# Connectors.net
KiCad netlist of a schematic drawn in Altium Designer
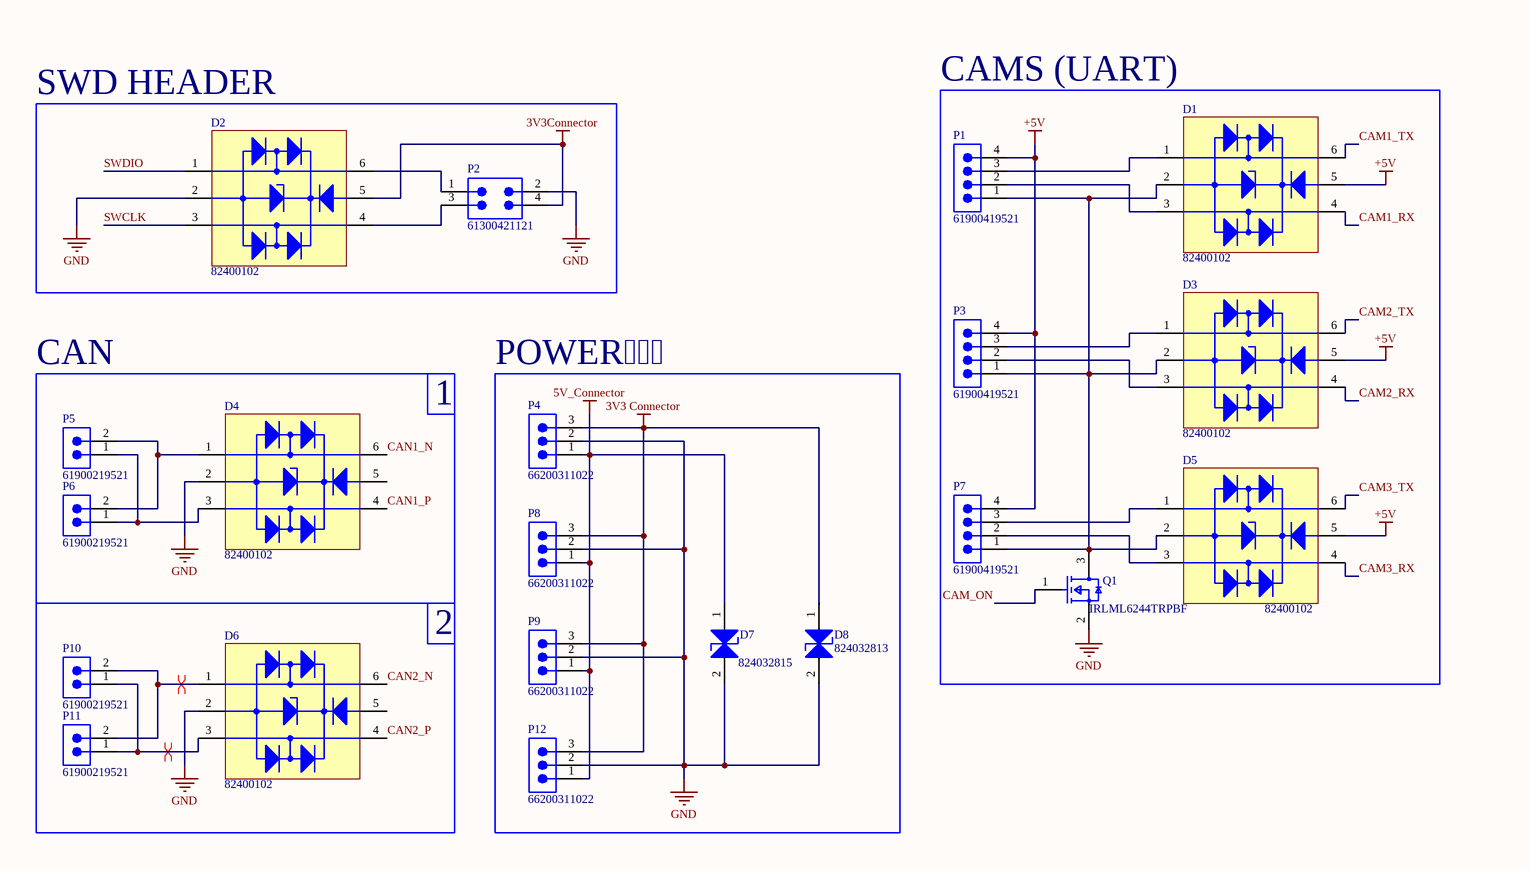
[diagram p0: Connectors.SchDoc, left]
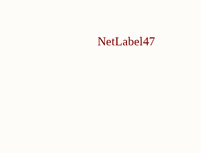
[diagram p1: Connectors.SchDoc, right]

(export (version "E")
  (design (tool "Eeschema 10.0.6"))
  (components
    (comp (ref "D1")
      (value "82400102")
      (footprint "WE-TVS_SOT23-6L")
      (description "WE-TVS TVS Diode – High Speed Series, SOT23-6L, 2+1 Channel, 5V, 2pF")
      (fields (field (name "MANUFACTURER") "Wurth Elektronik"))
      (libsource (lib "LEEM UPM") (part "82400152"))
    )
    (comp (ref "D2")
      (value "82400102")
      (footprint "WE-TVS_SOT23-6L")
      (description "WE-TVS TVS Diode – High Speed Series, SOT23-6L, 2+1 Channel, 5V, 2pF")
      (fields (field (name "MANUFACTURER") "Wurth Elektronik"))
      (libsource (lib "LEEM UPM") (part "82400152"))
    )
    (comp (ref "D3")
      (value "82400102")
      (footprint "WE-TVS_SOT23-6L")
      (description "WE-TVS TVS Diode – High Speed Series, SOT23-6L, 2+1 Channel, 5V, 2pF")
      (fields (field (name "MANUFACTURER") "Wurth Elektronik"))
      (libsource (lib "LEEM UPM") (part "82400152"))
    )
    (comp (ref "D4")
      (value "82400102")
      (footprint "WE-TVS_SOT23-6L")
      (description "WE-TVS TVS Diode – High Speed Series, SOT23-6L, 2+1 Channel, 5V, 2pF")
      (fields (field (name "MANUFACTURER") "Wurth Elektronik"))
      (libsource (lib "LEEM UPM") (part "82400152"))
    )
    (comp (ref "D5")
      (value "82400102")
      (footprint "WE-TVS_SOT23-6L")
      (description "WE-TVS TVS Diode – High Speed Series, SOT23-6L, 2+1 Channel, 5V, 2pF")
      (fields (field (name "MANUFACTURER") "Wurth Elektronik"))
      (libsource (lib "LEEM UPM") (part "82400152"))
    )
    (comp (ref "D6")
      (value "82400102")
      (footprint "WE-TVS_SOT23-6L")
      (description "WE-TVS TVS Diode – High Speed Series, SOT23-6L, 2+1 Channel, 5V, 2pF")
      (fields (field (name "MANUFACTURER") "Wurth Elektronik"))
      (libsource (lib "LEEM UPM") (part "82400152"))
    )
    (comp (ref "D7")
      (value "824032815")
      (footprint "WE-TVS_DFN1610-2L")
      (description "824032815 Tvs Diode, Bidir, 5V, Dfn1610 Rohs Compliant: Yes")
      (libsource (lib "Altium Content Vault") (part "Diode_1 Channel_Bidirectional"))
    )
    (comp (ref "D8")
      (value "824032813")
      (footprint "WE-TVS_DFN1610-2L")
      (description "824032813 Tvs Diode, Bidir, 3.3V, Dfn1610 Rohs Compliant: Yes")
      (libsource (lib "Altium Content Vault") (part "Diode_1 Channel_Bidirectional"))
    )
    (comp (ref "P1")
      (value "61900419521")
      (footprint "61900419521")
      (description "WR-WTB THT Male Right Angled Top Locking Header, pitch 2.54mm, 4pins")
      (fields (field (name "MANUFACTURER") "Wurth Elektronik"))
      (libsource (lib "LEEM UPM") (part "679304124022"))
    )
    (comp (ref "P2")
      (value "61300421121")
      (footprint "61300421121")
      (libsource (lib "LEEM UPM") (part "Header_Male_2R_04P"))
    )
    (comp (ref "P3")
      (value "61900419521")
      (footprint "61900419521")
      (description "WR-WTB THT Male Right Angled Top Locking Header, pitch 2.54mm, 4pins")
      (fields (field (name "MANUFACTURER") "Wurth Elektronik"))
      (libsource (lib "LEEM UPM") (part "679304124022"))
    )
    (comp (ref "P4")
      (value "66200311022")
      (footprint "66200311022")
      (description "WR-MPC3 THT Male Right Angled Header with Plastic Pegs, pitch 3mm, 3p")
      (fields (field (name "MANUFACTURER") "Wurth Elektronik"))
      (libsource (lib "LEEM UPM") (part "662303135922"))
    )
    (comp (ref "P5")
      (value "61900219521")
      (footprint "61900219521")
      (description "WR-WTB THT Male Right Angled Top Locking Header, pitch 2.54mm, 2pins")
      (fields (field (name "MANUFACTURER") "Wurth Elektronik"))
      (libsource (lib "LEEM UPM") (part "679302124022"))
    )
    (comp (ref "P6")
      (value "61900219521")
      (footprint "61900219521")
      (description "WR-WTB THT Male Right Angled Top Locking Header, pitch 2.54mm, 2pins")
      (fields (field (name "MANUFACTURER") "Wurth Elektronik"))
      (libsource (lib "LEEM UPM") (part "679302124022"))
    )
    (comp (ref "P7")
      (value "61900419521")
      (footprint "61900419521")
      (description "WR-WTB THT Male Right Angled Top Locking Header, pitch 2.54mm, 4pins")
      (fields (field (name "MANUFACTURER") "Wurth Elektronik"))
      (libsource (lib "LEEM UPM") (part "679304124022"))
    )
    (comp (ref "P8")
      (value "66200311022")
      (footprint "66200311022")
      (description "WR-MPC3 THT Male Right Angled Header with Plastic Pegs, pitch 3mm, 3p")
      (fields (field (name "MANUFACTURER") "Wurth Elektronik"))
      (libsource (lib "LEEM UPM") (part "662303135922"))
    )
    (comp (ref "P9")
      (value "66200311022")
      (footprint "66200311022")
      (description "WR-MPC3 THT Male Right Angled Header with Plastic Pegs, pitch 3mm, 3p")
      (fields (field (name "MANUFACTURER") "Wurth Elektronik"))
      (libsource (lib "LEEM UPM") (part "662303135922"))
    )
    (comp (ref "P10")
      (value "61900219521")
      (footprint "61900219521")
      (description "WR-WTB THT Male Right Angled Top Locking Header, pitch 2.54mm, 2pins")
      (fields (field (name "MANUFACTURER") "Wurth Elektronik"))
      (libsource (lib "LEEM UPM") (part "679302124022"))
    )
    (comp (ref "P11")
      (value "61900219521")
      (footprint "61900219521")
      (description "WR-WTB THT Male Right Angled Top Locking Header, pitch 2.54mm, 2pins")
      (fields (field (name "MANUFACTURER") "Wurth Elektronik"))
      (libsource (lib "LEEM UPM") (part "679302124022"))
    )
    (comp (ref "P12")
      (value "66200311022")
      (footprint "66200311022")
      (description "WR-MPC3 THT Male Right Angled Header with Plastic Pegs, pitch 3mm, 3p")
      (fields (field (name "MANUFACTURER") "Wurth Elektronik"))
      (libsource (lib "LEEM UPM") (part "662303135922"))
    )
    (comp (ref "Q1")
      (value "IRLML6244TRPBF")
      (footprint "FP-Micro3-IPC_C")
      (libsource (lib "LEEM UPM") (part "3b9c635fedb024a5347a57b145af9cc"))
    )
  )
  (nets
    (net (code "1") (name "+5V") (class "Default")
      (node (ref "D1") (pin "5") (pinfunction "VDD_5") (pintype "passive"))
      (node (ref "D3") (pin "5") (pinfunction "VDD_5") (pintype "passive"))
      (node (ref "D5") (pin "5") (pinfunction "VDD_5") (pintype "passive"))
      (node (ref "P1") (pin "4") (pinfunction "4_4") (pintype "passive"))
      (node (ref "P3") (pin "4") (pinfunction "4_4") (pintype "passive"))
      (node (ref "P7") (pin "4") (pinfunction "4_4") (pintype "passive"))
    )
    (net (code "2") (name "/CAM1_RX") (class "Default")
      (node (ref "D1") (pin "4") (pinfunction "I/O_2_4") (pintype "passive"))
    )
    (net (code "3") (name "/CAM1_TX") (class "Default")
      (node (ref "D1") (pin "6") (pinfunction "I/O_1_6") (pintype "passive"))
    )
    (net (code "4") (name "/CAM2_RX") (class "Default")
      (node (ref "D3") (pin "4") (pinfunction "I/O_2_4") (pintype "passive"))
    )
    (net (code "5") (name "/CAM2_TX") (class "Default")
      (node (ref "D3") (pin "6") (pinfunction "I/O_1_6") (pintype "passive"))
    )
    (net (code "6") (name "/CAM3_RX") (class "Default")
      (node (ref "D5") (pin "4") (pinfunction "I/O_2_4") (pintype "passive"))
    )
    (net (code "7") (name "/CAM3_TX") (class "Default")
      (node (ref "D5") (pin "6") (pinfunction "I/O_1_6") (pintype "passive"))
    )
    (net (code "8") (name "/CAM_ON") (class "Default")
      (node (ref "Q1") (pin "1") (pinfunction "G_1") (pintype "passive"))
    )
    (net (code "9") (name "/CAN1_N") (class "Default")
      (node (ref "D4") (pin "6") (pinfunction "I/O_1_6") (pintype "passive"))
    )
    (net (code "10") (name "/CAN1_P") (class "Default")
      (node (ref "D4") (pin "4") (pinfunction "I/O_2_4") (pintype "passive"))
    )
    (net (code "11") (name "/CAN2_N") (class "Default")
      (node (ref "D6") (pin "6") (pinfunction "I/O_1_6") (pintype "passive"))
    )
    (net (code "12") (name "/CAN2_P") (class "Default")
      (node (ref "D6") (pin "4") (pinfunction "I/O_2_4") (pintype "passive"))
    )
    (net (code "14") (name "/SWCLK") (class "Default")
      (node (ref "D2") (pin "3") (pinfunction "I/O_2_3") (pintype "passive"))
    )
    (net (code "15") (name "/SWDIO") (class "Default")
      (node (ref "D2") (pin "1") (pinfunction "I/O_1_1") (pintype "passive"))
    )
    (net (code "16") (name "3V3 Connector") (class "Default")
      (node (ref "D8") (pin "1") (pinfunction "I/O_1_1") (pintype "passive"))
      (node (ref "P12") (pin "3") (pinfunction "3_3") (pintype "passive"))
      (node (ref "P4") (pin "3") (pinfunction "3_3") (pintype "passive"))
      (node (ref "P8") (pin "3") (pinfunction "3_3") (pintype "passive"))
      (node (ref "P9") (pin "3") (pinfunction "3_3") (pintype "passive"))
    )
    (net (code "17") (name "3V3Connector") (class "Default")
      (node (ref "D2") (pin "5") (pinfunction "VDD_5") (pintype "passive"))
      (node (ref "P2") (pin "4") (pinfunction "4_4") (pintype "passive"))
    )
    (net (code "18") (name "5V_Connector") (class "Default")
      (node (ref "D7") (pin "1") (pinfunction "I/O_1_1") (pintype "passive"))
      (node (ref "P12") (pin "1") (pinfunction "1_1") (pintype "passive"))
      (node (ref "P4") (pin "1") (pinfunction "1_1") (pintype "passive"))
      (node (ref "P8") (pin "1") (pinfunction "1_1") (pintype "passive"))
      (node (ref "P9") (pin "1") (pinfunction "1_1") (pintype "passive"))
    )
    (net (code "19") (name "GND") (class "Default")
      (node (ref "D2") (pin "2") (pinfunction "GND_2") (pintype "passive"))
      (node (ref "D4") (pin "2") (pinfunction "GND_2") (pintype "passive"))
      (node (ref "D6") (pin "2") (pinfunction "GND_2") (pintype "passive"))
      (node (ref "D7") (pin "2") (pinfunction "GND_2") (pintype "passive"))
      (node (ref "D8") (pin "2") (pinfunction "GND_2") (pintype "passive"))
      (node (ref "P12") (pin "2") (pinfunction "2_2") (pintype "passive"))
      (node (ref "P2") (pin "2") (pinfunction "2_2") (pintype "passive"))
      (node (ref "P4") (pin "2") (pinfunction "2_2") (pintype "passive"))
      (node (ref "P8") (pin "2") (pinfunction "2_2") (pintype "passive"))
      (node (ref "P9") (pin "2") (pinfunction "2_2") (pintype "passive"))
      (node (ref "Q1") (pin "2") (pinfunction "S_2") (pintype "passive"))
    )
    (net (code "20") (name "Net-(D1-GND)") (class "Default")
      (node (ref "D1") (pin "2") (pinfunction "GND_2") (pintype "passive"))
      (node (ref "D3") (pin "2") (pinfunction "GND_2") (pintype "passive"))
      (node (ref "D5") (pin "2") (pinfunction "GND_2") (pintype "passive"))
      (node (ref "P1") (pin "1") (pinfunction "1_1") (pintype "passive"))
      (node (ref "P3") (pin "1") (pinfunction "1_1") (pintype "passive"))
      (node (ref "P7") (pin "1") (pinfunction "1_1") (pintype "passive"))
      (node (ref "Q1") (pin "3") (pinfunction "D_3") (pintype "passive"))
    )
    (net (code "21") (name "Net-(D1-I{slash}O_1-Pad1)") (class "Default")
      (node (ref "D1") (pin "1") (pinfunction "I/O_1_1") (pintype "passive"))
      (node (ref "P1") (pin "3") (pinfunction "3_3") (pintype "passive"))
    )
    (net (code "22") (name "Net-(D1-I{slash}O_2-Pad3)") (class "Default")
      (node (ref "D1") (pin "3") (pinfunction "I/O_2_3") (pintype "passive"))
      (node (ref "P1") (pin "2") (pinfunction "2_2") (pintype "passive"))
    )
    (net (code "23") (name "Net-(D2-I{slash}O_1-Pad6)") (class "Default")
      (node (ref "D2") (pin "6") (pinfunction "I/O_1_6") (pintype "passive"))
      (node (ref "P2") (pin "1") (pinfunction "1_1") (pintype "passive"))
    )
    (net (code "24") (name "Net-(D2-I{slash}O_2-Pad4)") (class "Default")
      (node (ref "D2") (pin "4") (pinfunction "I/O_2_4") (pintype "passive"))
      (node (ref "P2") (pin "3") (pinfunction "3_3") (pintype "passive"))
    )
    (net (code "25") (name "Net-(D3-I{slash}O_1-Pad1)") (class "Default")
      (node (ref "D3") (pin "1") (pinfunction "I/O_1_1") (pintype "passive"))
      (node (ref "P3") (pin "3") (pinfunction "3_3") (pintype "passive"))
    )
    (net (code "26") (name "Net-(D3-I{slash}O_2-Pad3)") (class "Default")
      (node (ref "D3") (pin "3") (pinfunction "I/O_2_3") (pintype "passive"))
      (node (ref "P3") (pin "2") (pinfunction "2_2") (pintype "passive"))
    )
    (net (code "27") (name "Net-(D4-I{slash}O_1-Pad1)") (class "Default")
      (node (ref "D4") (pin "1") (pinfunction "I/O_1_1") (pintype "passive"))
      (node (ref "P5") (pin "2") (pinfunction "2_2") (pintype "passive"))
      (node (ref "P6") (pin "2") (pinfunction "2_2") (pintype "passive"))
    )
    (net (code "28") (name "Net-(D4-I{slash}O_2-Pad3)") (class "Default")
      (node (ref "D4") (pin "3") (pinfunction "I/O_2_3") (pintype "passive"))
      (node (ref "P5") (pin "1") (pinfunction "1_1") (pintype "passive"))
      (node (ref "P6") (pin "1") (pinfunction "1_1") (pintype "passive"))
    )
    (net (code "29") (name "Net-(D5-I{slash}O_1-Pad1)") (class "Default")
      (node (ref "D5") (pin "1") (pinfunction "I/O_1_1") (pintype "passive"))
      (node (ref "P7") (pin "3") (pinfunction "3_3") (pintype "passive"))
    )
    (net (code "30") (name "Net-(D5-I{slash}O_2-Pad3)") (class "Default")
      (node (ref "D5") (pin "3") (pinfunction "I/O_2_3") (pintype "passive"))
      (node (ref "P7") (pin "2") (pinfunction "2_2") (pintype "passive"))
    )
    (net (code "31") (name "Net-(D6-I{slash}O_1-Pad1)") (class "Default")
      (node (ref "D6") (pin "1") (pinfunction "I/O_1_1") (pintype "passive"))
      (node (ref "P10") (pin "2") (pinfunction "2_2") (pintype "passive"))
      (node (ref "P11") (pin "2") (pinfunction "2_2") (pintype "passive"))
    )
    (net (code "32") (name "Net-(D6-I{slash}O_2-Pad3)") (class "Default")
      (node (ref "D6") (pin "3") (pinfunction "I/O_2_3") (pintype "passive"))
      (node (ref "P10") (pin "1") (pinfunction "1_1") (pintype "passive"))
      (node (ref "P11") (pin "1") (pinfunction "1_1") (pintype "passive"))
    )
    (net (code "33") (name "unconnected-(D4-VDD-Pad5)") (class "Default")
      (node (ref "D4") (pin "5") (pinfunction "VDD_5") (pintype "passive"))
    )
    (net (code "34") (name "unconnected-(D6-VDD-Pad5)") (class "Default")
      (node (ref "D6") (pin "5") (pinfunction "VDD_5") (pintype "passive"))
    )
  )
)
